# ProPrj_ms5837holder_2026-05-16.net
KiCad netlist of a schematic drawn in EasyEDA Pro
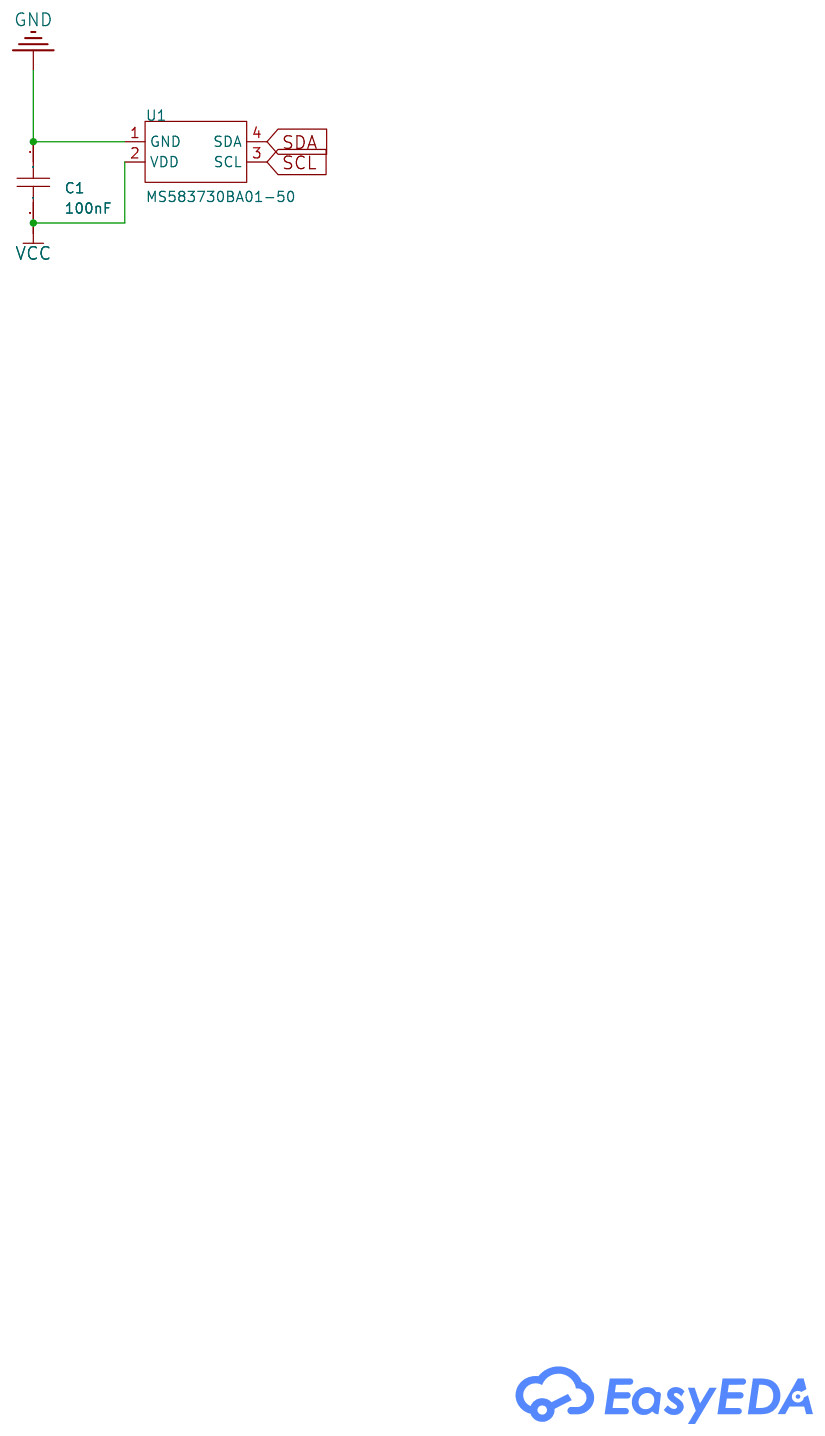
[diagram p0: schematic sheet]

(export (version "E")
  (design (tool "Eeschema 10.0.6"))
  (components
    (comp (ref "C1")
      (value "100nF")
      (footprint "easyedapro:C0402")
      (description "Capacitance:100nF Tolerance:±10% Tolerance:±10% Voltage Rating:50V Temperature Coefficient:X7R")
      (fields
        (field (name "Manufacturer Part") "CL05B104KB54PNC")
        (field (name "Manufacturer") "SAMSUNG(三星)")
      )
      (libsource (lib "easyedapro") (part "CL05B104KB54PNC"))
    )
    (comp (ref "U1")
      (value "MS583730BA01-50")
      (footprint "easyedapro:SENSOR-SMD_4P-L3.3-W3.3-P2.00-BL")
      (fields (field (name "Manufacturer") "TE Connectivity(泰科电子)"))
      (libsource (lib "easyedapro") (part "MS583730BA01-50"))
    )
  )
  (nets
    (net (code "1") (name "GND") (class "Default")
      (node (ref "C1") (pin "1") (pinfunction "1_1") (pintype "input"))
      (node (ref "U1") (pin "1") (pinfunction "GND_1") (pintype "unspecified"))
    )
    (net (code "2") (name "SCL") (class "Default")
      (node (ref "U1") (pin "3") (pinfunction "SCL_3") (pintype "unspecified"))
    )
    (net (code "3") (name "SDA") (class "Default")
      (node (ref "U1") (pin "4") (pinfunction "SDA_4") (pintype "unspecified"))
    )
    (net (code "4") (name "VCC") (class "Default")
      (node (ref "C1") (pin "2") (pinfunction "2_2") (pintype "input"))
      (node (ref "U1") (pin "2") (pinfunction "VDD_2") (pintype "unspecified"))
    )
  )
)
